# PRC-16105-AFC-1V1.net
KiCad netlist of a schematic drawn in EAGLE
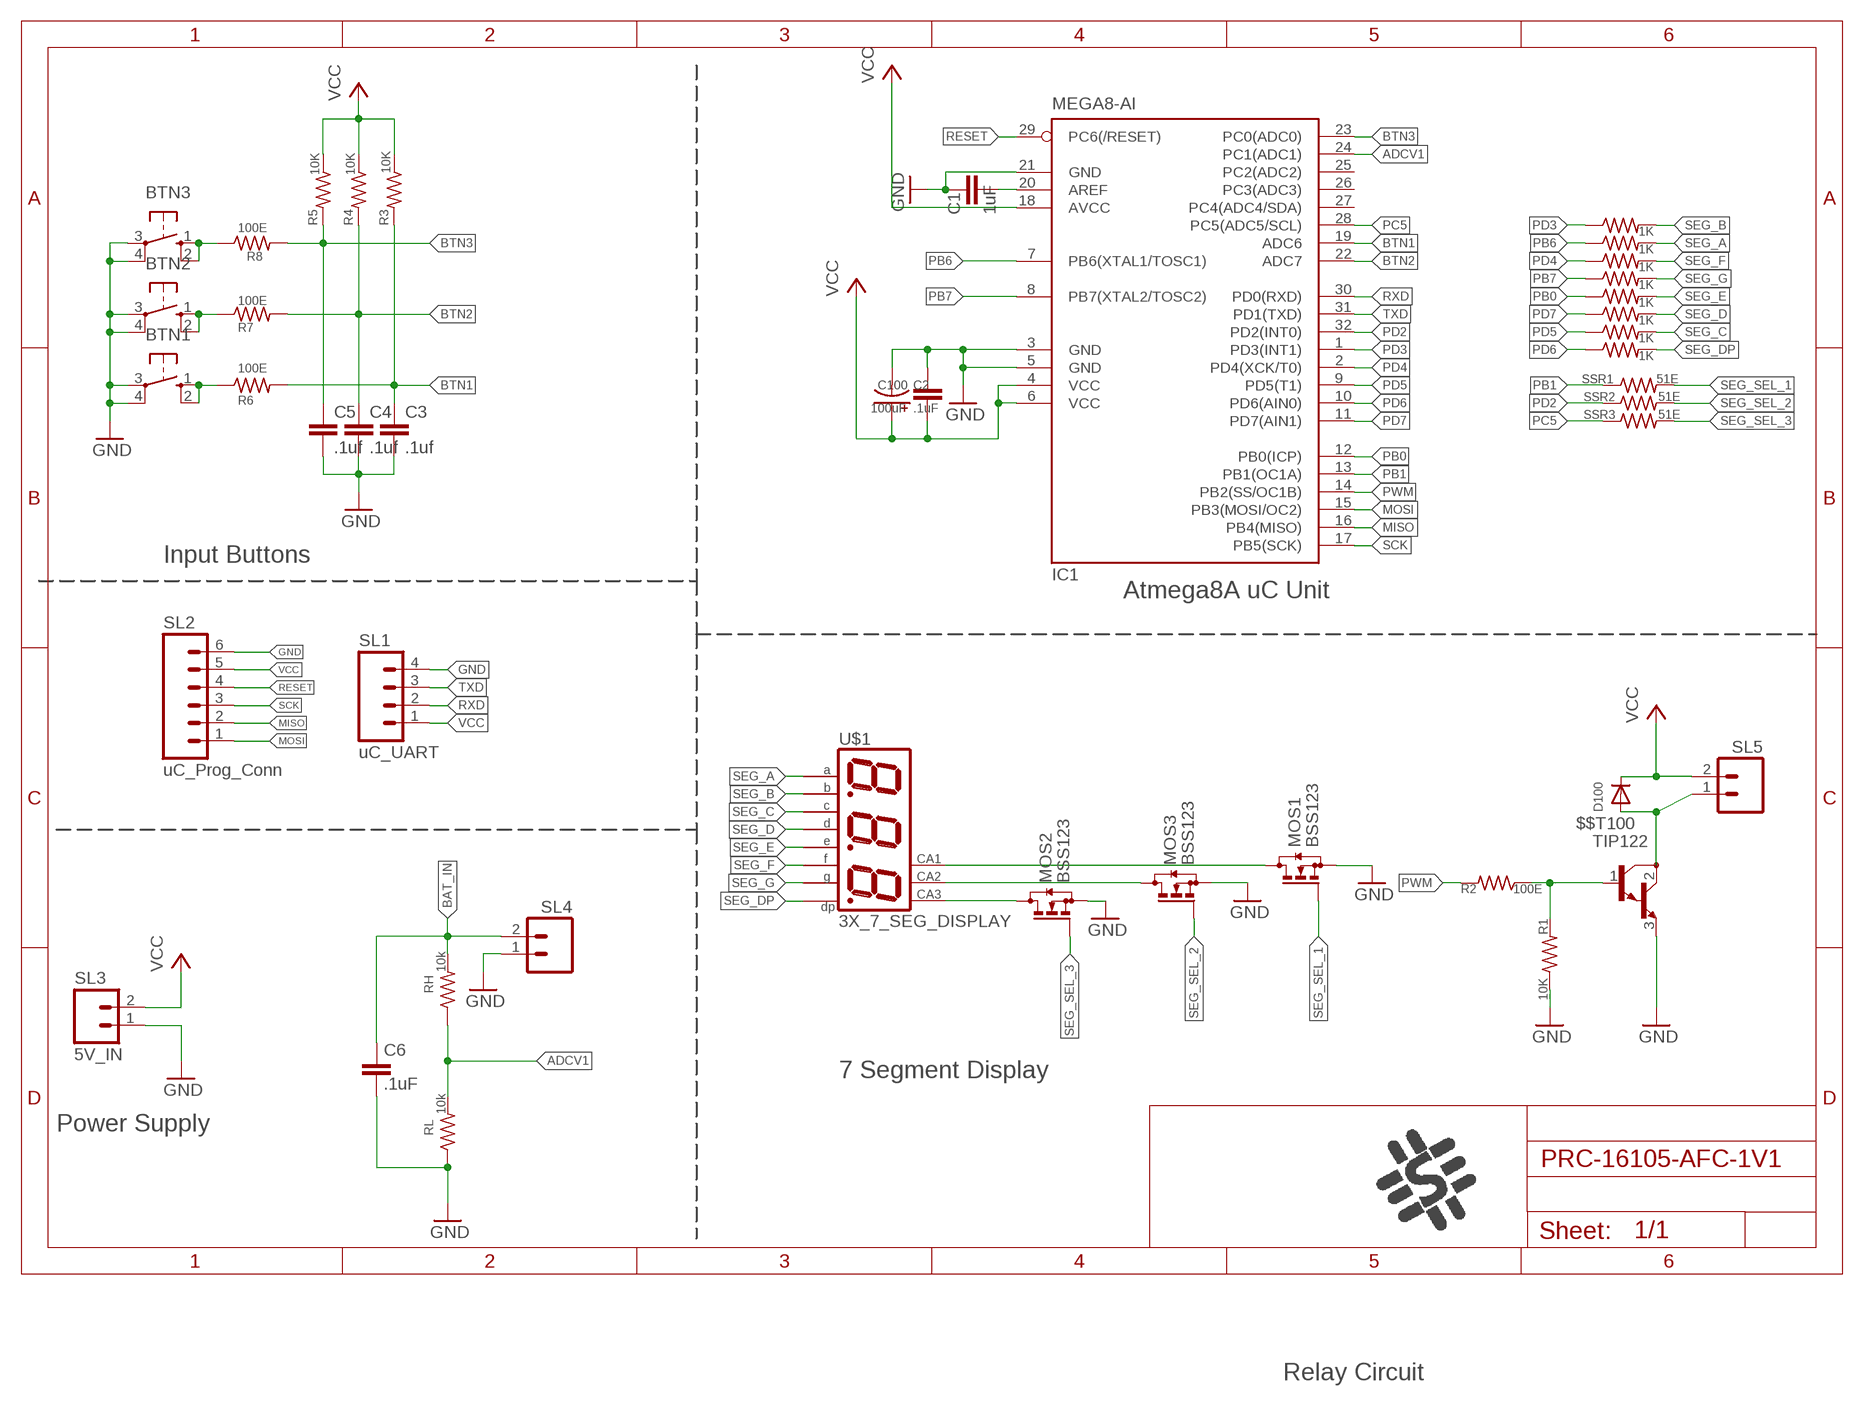
[diagram p0: schematic, sheet 1]

(export (version "E")
  (design (tool "Eeschema 10.0.6"))
  (components
    (comp (ref "$$T100")
      (value "TIP122")
      (footprint "eagle-import:TO220")
      (libsource (lib "eagle-import") (part "TIP122"))
    )
    (comp (ref "BTN1")
      (value "10-XX")
      (footprint "eagle-import:B3F-10XX")
      (fields (field (name "MPN") "B3F-1000"))
      (libsource (lib "eagle-import") (part "10-XX"))
    )
    (comp (ref "BTN2")
      (value "10-XX")
      (footprint "eagle-import:B3F-10XX")
      (fields (field (name "MPN") "B3F-1000"))
      (libsource (lib "eagle-import") (part "10-XX"))
    )
    (comp (ref "BTN3")
      (value "10-XX")
      (footprint "eagle-import:B3F-10XX")
      (fields (field (name "MPN") "B3F-1000"))
      (libsource (lib "eagle-import") (part "10-XX"))
    )
    (comp (ref "C1")
      (value "1uF")
      (footprint "eagle-import:C0603K")
      (libsource (lib "eagle-import") (part "resistor_C-EUC0603K"))
    )
    (comp (ref "C2")
      (value ".1uF")
      (footprint "eagle-import:C0603K")
      (libsource (lib "eagle-import") (part "C-EUC0603K"))
    )
    (comp (ref "C3")
      (value ".1uf")
      (footprint "eagle-import:C0603K")
      (libsource (lib "eagle-import") (part "resistor_C-EUC0603K"))
    )
    (comp (ref "C4")
      (value ".1uf")
      (footprint "eagle-import:C0603K")
      (libsource (lib "eagle-import") (part "resistor_C-EUC0603K"))
    )
    (comp (ref "C5")
      (value ".1uf")
      (footprint "eagle-import:C0603K")
      (libsource (lib "eagle-import") (part "resistor_C-EUC0603K"))
    )
    (comp (ref "C6")
      (value ".1uF")
      (footprint "eagle-import:C0603K")
      (libsource (lib "eagle-import") (part "C-EUC0603K"))
    )
    (comp (ref "C100")
      (value "100uF")
      (footprint "eagle-import:153CLV-0807")
      (libsource (lib "eagle-import") (part "CPOL-US153CLV-0807"))
    )
    (comp (ref "D100")
      (value "DIODESMA")
      (footprint "eagle-import:SMADIODE")
      (libsource (lib "eagle-import") (part "DIODESMA"))
    )
    (comp (ref "IC1")
      (value "MEGA8-AI")
      (footprint "eagle-import:TQFP32-08")
      (fields (field (name "MPN") "ATMEGA8-16AU"))
      (libsource (lib "eagle-import") (part "MEGA8-AI"))
    )
    (comp (ref "LOGO100")
      (value "SC_LOGO")
      (footprint "eagle-import:SC_LOGO")
      (libsource (lib "eagle-import") (part "SC_LOGO"))
    )
    (comp (ref "MOS1")
      (value "BSS123")
      (footprint "eagle-import:SOT23")
      (libsource (lib "eagle-import") (part "BSS123"))
    )
    (comp (ref "MOS2")
      (value "BSS123")
      (footprint "eagle-import:SOT23")
      (libsource (lib "eagle-import") (part "BSS123"))
    )
    (comp (ref "MOS3")
      (value "BSS123")
      (footprint "eagle-import:SOT23")
      (libsource (lib "eagle-import") (part "BSS123"))
    )
    (comp (ref "R1")
      (value "10K")
      (footprint "eagle-import:R0603")
      (libsource (lib "eagle-import") (part "R-US_R0603"))
    )
    (comp (ref "R2")
      (value "100E")
      (footprint "eagle-import:R0603")
      (libsource (lib "eagle-import") (part "R-US_R0603"))
    )
    (comp (ref "R3")
      (value "10K")
      (footprint "eagle-import:R0603")
      (libsource (lib "eagle-import") (part "R-US_R0603"))
    )
    (comp (ref "R4")
      (value "10K")
      (footprint "eagle-import:R0603")
      (libsource (lib "eagle-import") (part "R-US_R0603"))
    )
    (comp (ref "R5")
      (value "10K")
      (footprint "eagle-import:R0603")
      (libsource (lib "eagle-import") (part "R-US_R0603"))
    )
    (comp (ref "R6")
      (value "100E")
      (footprint "eagle-import:R0603")
      (libsource (lib "eagle-import") (part "R-US_R0603"))
    )
    (comp (ref "R7")
      (value "100E")
      (footprint "eagle-import:R0603")
      (libsource (lib "eagle-import") (part "R-US_R0603"))
    )
    (comp (ref "R8")
      (value "100E")
      (footprint "eagle-import:R0603")
      (libsource (lib "eagle-import") (part "R-US_R0603"))
    )
    (comp (ref "RB1")
      (value "1K")
      (footprint "eagle-import:R0603")
      (libsource (lib "eagle-import") (part "R-US_R0603"))
    )
    (comp (ref "RB2")
      (value "1K")
      (footprint "eagle-import:R0603")
      (libsource (lib "eagle-import") (part "R-US_R0603"))
    )
    (comp (ref "RB3")
      (value "1K")
      (footprint "eagle-import:R0603")
      (libsource (lib "eagle-import") (part "R-US_R0603"))
    )
    (comp (ref "RB4")
      (value "1K")
      (footprint "eagle-import:R0603")
      (libsource (lib "eagle-import") (part "R-US_R0603"))
    )
    (comp (ref "RB5")
      (value "1K")
      (footprint "eagle-import:R0603")
      (libsource (lib "eagle-import") (part "R-US_R0603"))
    )
    (comp (ref "RB6")
      (value "1K")
      (footprint "eagle-import:R0603")
      (libsource (lib "eagle-import") (part "R-US_R0603"))
    )
    (comp (ref "RB7")
      (value "1K")
      (footprint "eagle-import:R0603")
      (libsource (lib "eagle-import") (part "R-US_R0603"))
    )
    (comp (ref "RB8")
      (value "1K")
      (footprint "eagle-import:R0603")
      (libsource (lib "eagle-import") (part "R-US_R0603"))
    )
    (comp (ref "RH")
      (value "10k")
      (footprint "eagle-import:R0603")
      (libsource (lib "eagle-import") (part "R-US_R0603"))
    )
    (comp (ref "RL")
      (value "10k")
      (footprint "eagle-import:R0603")
      (libsource (lib "eagle-import") (part "R-US_R0603"))
    )
    (comp (ref "SL1")
      (value "uC_UART")
      (footprint "eagle-import:04P")
      (libsource (lib "eagle-import") (part "M04"))
    )
    (comp (ref "SL2")
      (value "uC_Prog_Conn")
      (footprint "eagle-import:06P")
      (libsource (lib "eagle-import") (part "M06"))
    )
    (comp (ref "SL3")
      (value "5V_IN")
      (footprint "eagle-import:02P")
      (libsource (lib "eagle-import") (part "M02"))
    )
    (comp (ref "SL4")
      (value "M02")
      (footprint "eagle-import:02P")
      (libsource (lib "eagle-import") (part "M02"))
    )
    (comp (ref "SL5")
      (value "M02")
      (footprint "eagle-import:02P")
      (libsource (lib "eagle-import") (part "M02"))
    )
    (comp (ref "SSR1")
      (value "51E")
      (footprint "eagle-import:R0603")
      (libsource (lib "eagle-import") (part "R-US_R0603"))
    )
    (comp (ref "SSR2")
      (value "51E")
      (footprint "eagle-import:R0603")
      (libsource (lib "eagle-import") (part "R-US_R0603"))
    )
    (comp (ref "SSR3")
      (value "51E")
      (footprint "eagle-import:R0603")
      (libsource (lib "eagle-import") (part "R-US_R0603"))
    )
    (comp (ref "U$1")
      (value "3X_7_SEG_DISPLAY")
      (footprint "eagle-import:SP36012CR")
      (libsource (lib "eagle-import") (part "3X_7_SEG_DISPLAY"))
    )
  )
  (nets
    (net (code "1") (name "ADCV1") (class "Default")
      (node (ref "IC1") (pin "24") (pinfunction "PC1(ADC1)_24") (pintype "bidirectional"))
      (node (ref "RH") (pin "1") (pinfunction "1_1") (pintype "passive"))
      (node (ref "RL") (pin "2") (pinfunction "2_2") (pintype "passive"))
    )
    (net (code "2") (name "BAT_IN") (class "Default")
      (node (ref "C6") (pin "1") (pinfunction "1_1") (pintype "passive"))
      (node (ref "RH") (pin "2") (pinfunction "2_2") (pintype "passive"))
      (node (ref "SL4") (pin "2") (pinfunction "2_2") (pintype "passive"))
    )
    (net (code "3") (name "BTN1") (class "Default")
      (node (ref "C3") (pin "1") (pinfunction "1_1") (pintype "passive"))
      (node (ref "IC1") (pin "19") (pinfunction "ADC6_19") (pintype "bidirectional"))
      (node (ref "R3") (pin "2") (pinfunction "2_2") (pintype "passive"))
      (node (ref "R6") (pin "2") (pinfunction "2_2") (pintype "passive"))
    )
    (net (code "4") (name "BTN2") (class "Default")
      (node (ref "C4") (pin "1") (pinfunction "1_1") (pintype "passive"))
      (node (ref "IC1") (pin "22") (pinfunction "ADC7_22") (pintype "bidirectional"))
      (node (ref "R4") (pin "2") (pinfunction "2_2") (pintype "passive"))
      (node (ref "R7") (pin "2") (pinfunction "2_2") (pintype "passive"))
    )
    (net (code "5") (name "BTN3") (class "Default")
      (node (ref "C5") (pin "1") (pinfunction "1_1") (pintype "passive"))
      (node (ref "IC1") (pin "23") (pinfunction "PC0(ADC0)_23") (pintype "bidirectional"))
      (node (ref "R5") (pin "2") (pinfunction "2_2") (pintype "passive"))
      (node (ref "R8") (pin "2") (pinfunction "2_2") (pintype "passive"))
    )
    (net (code "6") (name "GND") (class "Default")
      (node (ref "$$T100") (pin "3") (pinfunction "E_3") (pintype "passive"))
      (node (ref "BTN1") (pin "3") (pinfunction "P_3") (pintype "passive"))
      (node (ref "BTN1") (pin "4") (pinfunction "P1_4") (pintype "passive"))
      (node (ref "BTN2") (pin "3") (pinfunction "P_3") (pintype "passive"))
      (node (ref "BTN2") (pin "4") (pinfunction "P1_4") (pintype "passive"))
      (node (ref "BTN3") (pin "3") (pinfunction "P_3") (pintype "passive"))
      (node (ref "BTN3") (pin "4") (pinfunction "P1_4") (pintype "passive"))
      (node (ref "C1") (pin "1") (pinfunction "1_1") (pintype "passive"))
      (node (ref "C100") (pin "-") (pinfunction "-_-") (pintype "passive"))
      (node (ref "C2") (pin "2") (pinfunction "2_2") (pintype "passive"))
      (node (ref "C3") (pin "2") (pinfunction "2_2") (pintype "passive"))
      (node (ref "C4") (pin "2") (pinfunction "2_2") (pintype "passive"))
      (node (ref "C5") (pin "2") (pinfunction "2_2") (pintype "passive"))
      (node (ref "C6") (pin "2") (pinfunction "2_2") (pintype "passive"))
      (node (ref "IC1") (pin "21") (pinfunction "GND_21") (pintype "power_in"))
      (node (ref "IC1") (pin "3") (pinfunction "GND_3") (pintype "power_in"))
      (node (ref "IC1") (pin "5") (pinfunction "GND_5") (pintype "power_in"))
      (node (ref "MOS1") (pin "2") (pinfunction "S_2") (pintype "passive"))
      (node (ref "MOS2") (pin "2") (pinfunction "S_2") (pintype "passive"))
      (node (ref "MOS3") (pin "2") (pinfunction "S_2") (pintype "passive"))
      (node (ref "R1") (pin "1") (pinfunction "1_1") (pintype "passive"))
      (node (ref "RL") (pin "1") (pinfunction "1_1") (pintype "passive"))
      (node (ref "SL1") (pin "4") (pinfunction "4_4") (pintype "passive"))
      (node (ref "SL2") (pin "6") (pinfunction "6_6") (pintype "passive"))
      (node (ref "SL3") (pin "1") (pinfunction "1_1") (pintype "passive"))
      (node (ref "SL4") (pin "1") (pinfunction "1_1") (pintype "passive"))
    )
    (net (code "7") (name "MISO") (class "Default")
      (node (ref "IC1") (pin "16") (pinfunction "PB4(MISO)_16") (pintype "bidirectional"))
      (node (ref "SL2") (pin "2") (pinfunction "2_2") (pintype "passive"))
    )
    (net (code "8") (name "MOSI") (class "Default")
      (node (ref "IC1") (pin "15") (pinfunction "PB3(MOSI/OC2)_15") (pintype "bidirectional"))
      (node (ref "SL2") (pin "1") (pinfunction "1_1") (pintype "passive"))
    )
    (net (code "9") (name "Net-($$T100-B)") (class "Default")
      (node (ref "$$T100") (pin "1") (pinfunction "B_1") (pintype "passive"))
      (node (ref "R1") (pin "2") (pinfunction "2_2") (pintype "passive"))
      (node (ref "R2") (pin "1") (pinfunction "1_1") (pintype "passive"))
    )
    (net (code "10") (name "Net-($$T100-C)") (class "Default")
      (node (ref "$$T100") (pin "2") (pinfunction "C_2") (pintype "passive"))
      (node (ref "D100") (pin "A") (pinfunction "A_A") (pintype "passive"))
      (node (ref "SL5") (pin "1") (pinfunction "1_1") (pintype "passive"))
    )
    (net (code "11") (name "Net-(BTN1-S)") (class "Default")
      (node (ref "BTN1") (pin "1") (pinfunction "S_1") (pintype "passive"))
      (node (ref "BTN1") (pin "2") (pinfunction "S1_2") (pintype "passive"))
      (node (ref "R6") (pin "1") (pinfunction "1_1") (pintype "passive"))
    )
    (net (code "12") (name "Net-(BTN2-S)") (class "Default")
      (node (ref "BTN2") (pin "1") (pinfunction "S_1") (pintype "passive"))
      (node (ref "BTN2") (pin "2") (pinfunction "S1_2") (pintype "passive"))
      (node (ref "R7") (pin "1") (pinfunction "1_1") (pintype "passive"))
    )
    (net (code "13") (name "Net-(BTN3-S)") (class "Default")
      (node (ref "BTN3") (pin "1") (pinfunction "S_1") (pintype "passive"))
      (node (ref "BTN3") (pin "2") (pinfunction "S1_2") (pintype "passive"))
      (node (ref "R8") (pin "1") (pinfunction "1_1") (pintype "passive"))
    )
    (net (code "14") (name "Net-(IC1-AREF)") (class "Default")
      (node (ref "C1") (pin "2") (pinfunction "2_2") (pintype "passive"))
      (node (ref "IC1") (pin "20") (pinfunction "AREF_20") (pintype "passive"))
    )
    (net (code "15") (name "Net-(MOS1-D)") (class "Default")
      (node (ref "MOS1") (pin "3") (pinfunction "D_3") (pintype "passive"))
      (node (ref "U$1") (pin "12") (pinfunction "CA_12") (pintype "passive"))
    )
    (net (code "16") (name "Net-(MOS2-D)") (class "Default")
      (node (ref "MOS2") (pin "3") (pinfunction "D_3") (pintype "passive"))
      (node (ref "U$1") (pin "8") (pinfunction "CA_8") (pintype "passive"))
    )
    (net (code "17") (name "Net-(MOS3-D)") (class "Default")
      (node (ref "MOS3") (pin "3") (pinfunction "D_3") (pintype "passive"))
      (node (ref "U$1") (pin "9") (pinfunction "CA_9") (pintype "passive"))
    )
    (net (code "18") (name "PB0") (class "Default")
      (node (ref "IC1") (pin "12") (pinfunction "PB0(ICP)_12") (pintype "bidirectional"))
      (node (ref "RB1") (pin "1") (pinfunction "1_1") (pintype "passive"))
    )
    (net (code "19") (name "PB1") (class "Default")
      (node (ref "IC1") (pin "13") (pinfunction "PB1(OC1A)_13") (pintype "bidirectional"))
      (node (ref "SSR1") (pin "1") (pinfunction "1_1") (pintype "passive"))
    )
    (net (code "20") (name "PB6") (class "Default")
      (node (ref "IC1") (pin "7") (pinfunction "PB6(XTAL1/TOSC1)_7") (pintype "bidirectional"))
      (node (ref "RB6") (pin "1") (pinfunction "1_1") (pintype "passive"))
    )
    (net (code "21") (name "PB7") (class "Default")
      (node (ref "IC1") (pin "8") (pinfunction "PB7(XTAL2/TOSC2)_8") (pintype "bidirectional"))
      (node (ref "RB5") (pin "1") (pinfunction "1_1") (pintype "passive"))
    )
    (net (code "22") (name "PC5") (class "Default")
      (node (ref "IC1") (pin "28") (pinfunction "PC5(ADC5/SCL)_28") (pintype "bidirectional"))
      (node (ref "SSR3") (pin "1") (pinfunction "1_1") (pintype "passive"))
    )
    (net (code "23") (name "PD2") (class "Default")
      (node (ref "IC1") (pin "32") (pinfunction "PD2(INT0)_32") (pintype "bidirectional"))
      (node (ref "SSR2") (pin "1") (pinfunction "1_1") (pintype "passive"))
    )
    (net (code "24") (name "PD3") (class "Default")
      (node (ref "IC1") (pin "1") (pinfunction "PD3(INT1)_1") (pintype "bidirectional"))
      (node (ref "RB8") (pin "1") (pinfunction "1_1") (pintype "passive"))
    )
    (net (code "25") (name "PD4") (class "Default")
      (node (ref "IC1") (pin "2") (pinfunction "PD4(XCK/T0)_2") (pintype "bidirectional"))
      (node (ref "RB7") (pin "1") (pinfunction "1_1") (pintype "passive"))
    )
    (net (code "26") (name "PD5") (class "Default")
      (node (ref "IC1") (pin "9") (pinfunction "PD5(T1)_9") (pintype "bidirectional"))
      (node (ref "RB4") (pin "1") (pinfunction "1_1") (pintype "passive"))
    )
    (net (code "27") (name "PD6") (class "Default")
      (node (ref "IC1") (pin "10") (pinfunction "PD6(AIN0)_10") (pintype "bidirectional"))
      (node (ref "RB3") (pin "1") (pinfunction "1_1") (pintype "passive"))
    )
    (net (code "28") (name "PD7") (class "Default")
      (node (ref "IC1") (pin "11") (pinfunction "PD7(AIN1)_11") (pintype "bidirectional"))
      (node (ref "RB2") (pin "1") (pinfunction "1_1") (pintype "passive"))
    )
    (net (code "29") (name "PWM") (class "Default")
      (node (ref "IC1") (pin "14") (pinfunction "PB2(SS/OC1B)_14") (pintype "bidirectional"))
      (node (ref "R2") (pin "2") (pinfunction "2_2") (pintype "passive"))
    )
    (net (code "30") (name "RESET") (class "Default")
      (node (ref "IC1") (pin "29") (pinfunction "PC6(/RESET)_29") (pintype "bidirectional"))
      (node (ref "SL2") (pin "4") (pinfunction "4_4") (pintype "passive"))
    )
    (net (code "31") (name "RXD") (class "Default")
      (node (ref "IC1") (pin "30") (pinfunction "PD0(RXD)_30") (pintype "bidirectional"))
      (node (ref "SL1") (pin "2") (pinfunction "2_2") (pintype "passive"))
    )
    (net (code "32") (name "SCK") (class "Default")
      (node (ref "IC1") (pin "17") (pinfunction "PB5(SCK)_17") (pintype "bidirectional"))
      (node (ref "SL2") (pin "3") (pinfunction "3_3") (pintype "passive"))
    )
    (net (code "33") (name "SEG_A") (class "Default")
      (node (ref "RB6") (pin "2") (pinfunction "2_2") (pintype "passive"))
      (node (ref "U$1") (pin "11") (pinfunction "A_11") (pintype "passive"))
    )
    (net (code "34") (name "SEG_B") (class "Default")
      (node (ref "RB8") (pin "2") (pinfunction "2_2") (pintype "passive"))
      (node (ref "U$1") (pin "7") (pinfunction "B_7") (pintype "passive"))
    )
    (net (code "35") (name "SEG_C") (class "Default")
      (node (ref "RB4") (pin "2") (pinfunction "2_2") (pintype "passive"))
      (node (ref "U$1") (pin "4") (pinfunction "C_4") (pintype "passive"))
    )
    (net (code "36") (name "SEG_D") (class "Default")
      (node (ref "RB2") (pin "2") (pinfunction "2_2") (pintype "passive"))
      (node (ref "U$1") (pin "2") (pinfunction "D_2") (pintype "passive"))
    )
    (net (code "37") (name "SEG_DP") (class "Default")
      (node (ref "RB3") (pin "2") (pinfunction "2_2") (pintype "passive"))
      (node (ref "U$1") (pin "3") (pinfunction "DP_3") (pintype "passive"))
    )
    (net (code "38") (name "SEG_E") (class "Default")
      (node (ref "RB1") (pin "2") (pinfunction "2_2") (pintype "passive"))
      (node (ref "U$1") (pin "1") (pinfunction "E_1") (pintype "passive"))
    )
    (net (code "39") (name "SEG_F") (class "Default")
      (node (ref "RB7") (pin "2") (pinfunction "2_2") (pintype "passive"))
      (node (ref "U$1") (pin "10") (pinfunction "F_10") (pintype "passive"))
    )
    (net (code "40") (name "SEG_G") (class "Default")
      (node (ref "RB5") (pin "2") (pinfunction "2_2") (pintype "passive"))
      (node (ref "U$1") (pin "5") (pinfunction "G_5") (pintype "passive"))
    )
    (net (code "41") (name "SEG_SEL_1") (class "Default")
      (node (ref "MOS1") (pin "1") (pinfunction "G_1") (pintype "passive"))
      (node (ref "SSR1") (pin "2") (pinfunction "2_2") (pintype "passive"))
    )
    (net (code "42") (name "SEG_SEL_2") (class "Default")
      (node (ref "MOS3") (pin "1") (pinfunction "G_1") (pintype "passive"))
      (node (ref "SSR2") (pin "2") (pinfunction "2_2") (pintype "passive"))
    )
    (net (code "43") (name "SEG_SEL_3") (class "Default")
      (node (ref "MOS2") (pin "1") (pinfunction "G_1") (pintype "passive"))
      (node (ref "SSR3") (pin "2") (pinfunction "2_2") (pintype "passive"))
    )
    (net (code "44") (name "TXD") (class "Default")
      (node (ref "IC1") (pin "31") (pinfunction "PD1(TXD)_31") (pintype "bidirectional"))
      (node (ref "SL1") (pin "3") (pinfunction "3_3") (pintype "passive"))
    )
    (net (code "45") (name "VCC") (class "Default")
      (node (ref "C100") (pin "+") (pinfunction "+_+") (pintype "passive"))
      (node (ref "C2") (pin "1") (pinfunction "1_1") (pintype "passive"))
      (node (ref "D100") (pin "C") (pinfunction "C_C") (pintype "passive"))
      (node (ref "IC1") (pin "18") (pinfunction "AVCC_18") (pintype "power_in"))
      (node (ref "IC1") (pin "4") (pinfunction "VCC_4") (pintype "power_in"))
      (node (ref "IC1") (pin "6") (pinfunction "VCC_6") (pintype "power_in"))
      (node (ref "R3") (pin "1") (pinfunction "1_1") (pintype "passive"))
      (node (ref "R4") (pin "1") (pinfunction "1_1") (pintype "passive"))
      (node (ref "R5") (pin "1") (pinfunction "1_1") (pintype "passive"))
      (node (ref "SL1") (pin "1") (pinfunction "1_1") (pintype "passive"))
      (node (ref "SL2") (pin "5") (pinfunction "5_5") (pintype "passive"))
      (node (ref "SL3") (pin "2") (pinfunction "2_2") (pintype "passive"))
      (node (ref "SL5") (pin "2") (pinfunction "2_2") (pintype "passive"))
    )
    (net (code "46") (name "unconnected-(IC1-PC2(ADC2)-Pad25)") (class "Default")
      (node (ref "IC1") (pin "25") (pinfunction "PC2(ADC2)_25") (pintype "bidirectional"))
    )
    (net (code "47") (name "unconnected-(IC1-PC3(ADC3)-Pad26)") (class "Default")
      (node (ref "IC1") (pin "26") (pinfunction "PC3(ADC3)_26") (pintype "bidirectional"))
    )
    (net (code "48") (name "unconnected-(IC1-PC4(ADC4{slash}SDA)-Pad27)") (class "Default")
      (node (ref "IC1") (pin "27") (pinfunction "PC4(ADC4/SDA)_27") (pintype "bidirectional"))
    )
  )
)
